# GIC.net
KiCad netlist of a schematic drawn in Altium Designer
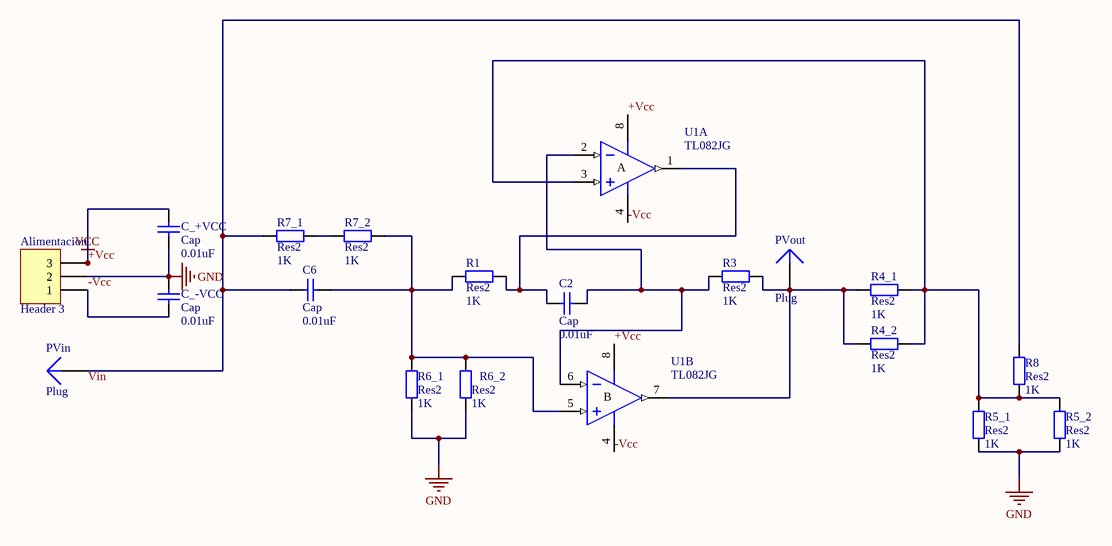
[diagram p0: GIC.SchDoc]

(export (version "E")
  (design (tool "Eeschema 10.0.6"))
  (components
    (comp (ref "Alimentacion")
      (value "Header 3")
      (footprint "HDR1X3")
      (description "Header, 3-Pin")
      (fields (field (name "PUBLISHER") "Altium Limited"))
      (libsource (lib "Miscellaneous Connectors") (part "Header 3"))
    )
    (comp (ref "C2")
      (value "Cap")
      (footprint "RAD-0.3")
      (description "Capacitor")
      (fields (field (name "ALTIUM_VALUE") "0.01uF") (field (name "PUBLISHER") "Altium Limited"))
      (libsource (lib "Miscellaneous Devices") (part "Cap"))
    )
    (comp (ref "C6")
      (value "Cap")
      (footprint "RAD-0.3")
      (description "Capacitor")
      (fields (field (name "ALTIUM_VALUE") "0.01uF") (field (name "PUBLISHER") "Altium Limited"))
      (libsource (lib "Miscellaneous Devices") (part "Cap"))
    )
    (comp (ref "C_+VCC")
      (value "Cap")
      (footprint "RAD-0.3")
      (description "Capacitor")
      (fields (field (name "ALTIUM_VALUE") "0.01uF") (field (name "PUBLISHER") "Altium Limited"))
      (libsource (lib "Miscellaneous Devices") (part "Cap"))
    )
    (comp (ref "C_-VCC")
      (value "Cap")
      (footprint "RAD-0.3")
      (description "Capacitor")
      (fields (field (name "ALTIUM_VALUE") "0.01uF") (field (name "PUBLISHER") "Altium Limited"))
      (libsource (lib "Miscellaneous Devices") (part "Cap"))
    )
    (comp (ref "PVin")
      (value "Plug")
      (footprint "PIN1")
      (fields (field (name "PUBLISHER") "Altium Limited"))
      (libsource (lib "Miscellaneous Connectors") (part "Plug"))
    )
    (comp (ref "PVout")
      (value "Plug")
      (footprint "PIN1")
      (fields (field (name "PUBLISHER") "Altium Limited"))
      (libsource (lib "Miscellaneous Connectors") (part "Plug"))
    )
    (comp (ref "R1")
      (value "Res2")
      (footprint "AXIAL-0.4")
      (description "Resistor")
      (fields (field (name "ALTIUM_VALUE") "1K") (field (name "PUBLISHER") "Altium Limited"))
      (libsource (lib "Miscellaneous Devices") (part "Res2"))
    )
    (comp (ref "R3")
      (value "Res2")
      (footprint "AXIAL-0.4")
      (description "Resistor")
      (fields (field (name "ALTIUM_VALUE") "1K") (field (name "PUBLISHER") "Altium Limited"))
      (libsource (lib "Miscellaneous Devices") (part "Res2"))
    )
    (comp (ref "R4_1")
      (value "Res2")
      (footprint "AXIAL-0.4")
      (description "Resistor")
      (fields (field (name "ALTIUM_VALUE") "1K") (field (name "PUBLISHER") "Altium Limited"))
      (libsource (lib "Miscellaneous Devices") (part "Res2"))
    )
    (comp (ref "R4_2")
      (value "Res2")
      (footprint "AXIAL-0.4")
      (description "Resistor")
      (fields (field (name "ALTIUM_VALUE") "1K") (field (name "PUBLISHER") "Altium Limited"))
      (libsource (lib "Miscellaneous Devices") (part "Res2"))
    )
    (comp (ref "R5_1")
      (value "Res2")
      (footprint "AXIAL-0.4")
      (description "Resistor")
      (fields (field (name "ALTIUM_VALUE") "1K") (field (name "PUBLISHER") "Altium Limited"))
      (libsource (lib "") (part "Res2_1"))
    )
    (comp (ref "R5_2")
      (value "Res2")
      (footprint "AXIAL-0.4")
      (description "Resistor")
      (fields (field (name "ALTIUM_VALUE") "1K") (field (name "PUBLISHER") "Altium Limited"))
      (libsource (lib "") (part "Res2_1"))
    )
    (comp (ref "R6_1")
      (value "Res2")
      (footprint "AXIAL-0.4")
      (description "Resistor")
      (fields (field (name "ALTIUM_VALUE") "1K") (field (name "PUBLISHER") "Altium Limited"))
      (libsource (lib "") (part "Res2_1"))
    )
    (comp (ref "R6_2")
      (value "Res2")
      (footprint "AXIAL-0.4")
      (description "Resistor")
      (fields (field (name "ALTIUM_VALUE") "1K") (field (name "PUBLISHER") "Altium Limited"))
      (libsource (lib "") (part "Res2_1"))
    )
    (comp (ref "R7_1")
      (value "Res2")
      (footprint "AXIAL-0.4")
      (description "Resistor")
      (fields (field (name "ALTIUM_VALUE") "1K") (field (name "PUBLISHER") "Altium Limited"))
      (libsource (lib "Miscellaneous Devices") (part "Res2"))
    )
    (comp (ref "R7_2")
      (value "Res2")
      (footprint "AXIAL-0.4")
      (description "Resistor")
      (fields (field (name "ALTIUM_VALUE") "1K") (field (name "PUBLISHER") "Altium Limited"))
      (libsource (lib "Miscellaneous Devices") (part "Res2"))
    )
    (comp (ref "R8")
      (value "Res2")
      (footprint "AXIAL-0.4")
      (description "Resistor")
      (fields (field (name "ALTIUM_VALUE") "1K") (field (name "PUBLISHER") "Altium Limited"))
      (libsource (lib "") (part "Res2_1"))
    )
    (comp (ref "U1")
      (value "TL082JG")
      (footprint "JG008")
      (description "JFET-Input Operational Amplifier")
      (fields (field (name "PUBLISHER") "Altium Limited"))
      (libsource (lib "TI Operational Amplifier") (part "TL082JG"))
    )
  )
  (nets
    (net (code "1") (name "/-Vcc") (class "Default")
      (node (ref "Alimentacion") (pin "1") (pinfunction "1_1") (pintype "passive"))
      (node (ref "C_-VCC") (pin "1") (pinfunction "1_1") (pintype "passive"))
      (node (ref "U1") (pin "4") (pinfunction "V-_4") (pintype "power_in"))
    )
    (net (code "3") (name "GND") (class "Default")
      (node (ref "Alimentacion") (pin "2") (pinfunction "2_2") (pintype "passive"))
      (node (ref "C_+VCC") (pin "1") (pinfunction "1_1") (pintype "passive"))
      (node (ref "C_-VCC") (pin "2") (pinfunction "2_2") (pintype "passive"))
      (node (ref "R5_1") (pin "1") (pinfunction "1_1") (pintype "passive"))
      (node (ref "R5_2") (pin "1") (pinfunction "1_1") (pintype "passive"))
      (node (ref "R6_1") (pin "1") (pinfunction "1_1") (pintype "passive"))
      (node (ref "R6_2") (pin "1") (pinfunction "1_1") (pintype "passive"))
    )
    (net (code "4") (name "Net-(C6-Pad2)") (class "Default")
      (node (ref "C6") (pin "2") (pinfunction "2_2") (pintype "passive"))
      (node (ref "PVin") (pin "1") (pinfunction "1_1") (pintype "passive"))
      (node (ref "R7_1") (pin "1") (pinfunction "1_1") (pintype "passive"))
      (node (ref "R8") (pin "2") (pinfunction "2_2") (pintype "passive"))
    )
    (net (code "5") (name "Net-(R7_1-Pad2)") (class "Default")
      (node (ref "R7_1") (pin "2") (pinfunction "2_2") (pintype "passive"))
      (node (ref "R7_2") (pin "1") (pinfunction "1_1") (pintype "passive"))
    )
    (net (code "6") (name "Net-(U1A-IN+)") (class "Default")
      (node (ref "R4_1") (pin "2") (pinfunction "2_2") (pintype "passive"))
      (node (ref "R4_2") (pin "2") (pinfunction "2_2") (pintype "passive"))
      (node (ref "R5_1") (pin "2") (pinfunction "2_2") (pintype "passive"))
      (node (ref "R5_2") (pin "2") (pinfunction "2_2") (pintype "passive"))
      (node (ref "R8") (pin "1") (pinfunction "1_1") (pintype "passive"))
      (node (ref "U1") (pin "3") (pinfunction "IN+_3") (pintype "input"))
    )
    (net (code "7") (name "Net-(U1A-IN-)") (class "Default")
      (node (ref "C2") (pin "2") (pinfunction "2_2") (pintype "passive"))
      (node (ref "R3") (pin "1") (pinfunction "1_1") (pintype "passive"))
      (node (ref "U1") (pin "2") (pinfunction "IN-_2") (pintype "input"))
      (node (ref "U1") (pin "6") (pinfunction "IN-_6") (pintype "input"))
    )
    (net (code "8") (name "Net-(U1A-OUT)") (class "Default")
      (node (ref "C2") (pin "1") (pinfunction "1_1") (pintype "passive"))
      (node (ref "R1") (pin "2") (pinfunction "2_2") (pintype "passive"))
      (node (ref "U1") (pin "1") (pinfunction "OUT_1") (pintype "output"))
    )
    (net (code "9") (name "Net-(U1B-IN+)") (class "Default")
      (node (ref "C6") (pin "1") (pinfunction "1_1") (pintype "passive"))
      (node (ref "R1") (pin "1") (pinfunction "1_1") (pintype "passive"))
      (node (ref "R6_1") (pin "2") (pinfunction "2_2") (pintype "passive"))
      (node (ref "R6_2") (pin "2") (pinfunction "2_2") (pintype "passive"))
      (node (ref "R7_2") (pin "2") (pinfunction "2_2") (pintype "passive"))
      (node (ref "U1") (pin "5") (pinfunction "IN+_5") (pintype "input"))
    )
    (net (code "10") (name "Net-(U1B-OUT)") (class "Default")
      (node (ref "PVout") (pin "1") (pinfunction "1_1") (pintype "passive"))
      (node (ref "R3") (pin "2") (pinfunction "2_2") (pintype "passive"))
      (node (ref "R4_1") (pin "1") (pinfunction "1_1") (pintype "passive"))
      (node (ref "R4_2") (pin "1") (pinfunction "1_1") (pintype "passive"))
      (node (ref "U1") (pin "7") (pinfunction "OUT_7") (pintype "output"))
    )
    (net (code "11") (name "VCC") (class "Default")
      (node (ref "Alimentacion") (pin "3") (pinfunction "3_3") (pintype "passive"))
      (node (ref "C_+VCC") (pin "2") (pinfunction "2_2") (pintype "passive"))
      (node (ref "U1") (pin "8") (pinfunction "V+_8") (pintype "power_in"))
    )
  )
)
